# LEDDimmerDuoMiniSwitchReg.net
KiCad netlist of a schematic drawn in EAGLE
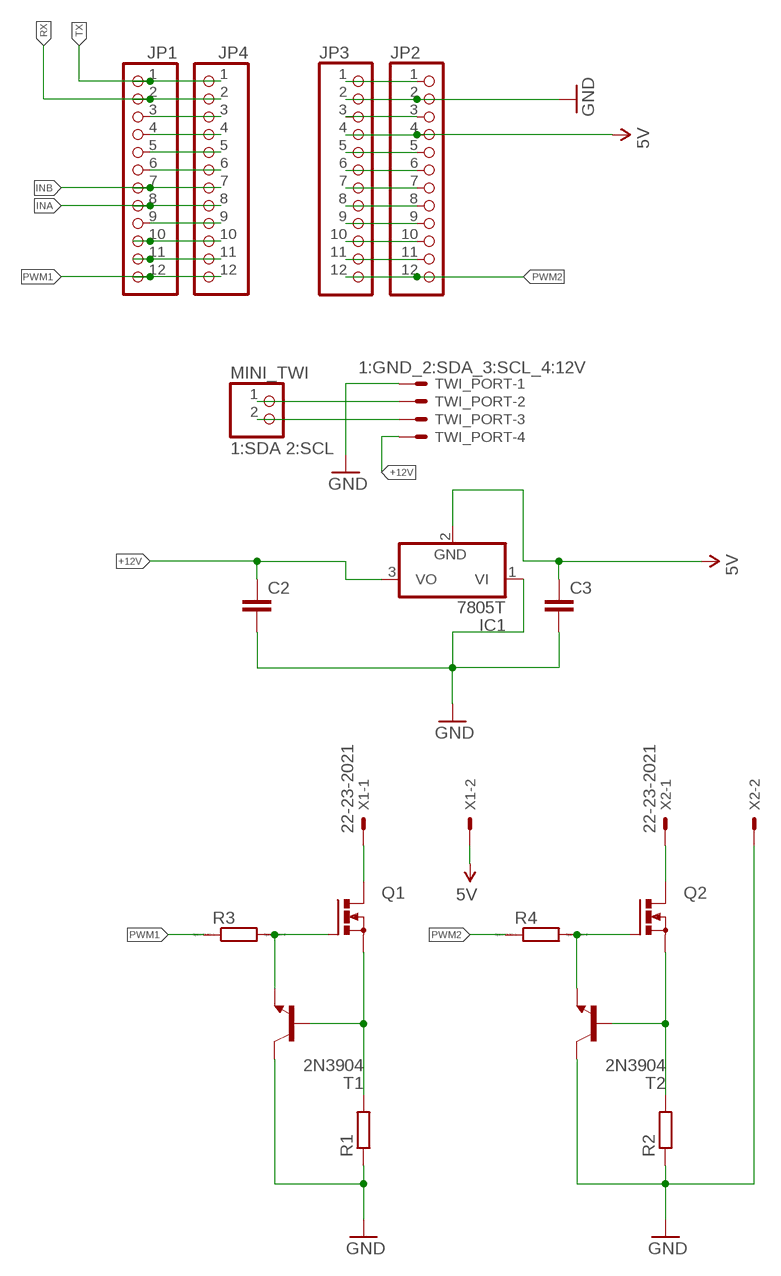
[diagram p0: schematic, sheet 1]

(export (version "E")
  (design (tool "Eeschema 10.0.6"))
  (components
    (comp (ref "C2")
      (value "CAP0603-CAP")
      (footprint "eagle-import:0603-CAP")
      (libsource (lib "eagle-import") (part "CAP0603-CAP"))
    )
    (comp (ref "C3")
      (value "CAP0603-CAP")
      (footprint "eagle-import:0603-CAP")
      (libsource (lib "eagle-import") (part "CAP0603-CAP"))
    )
    (comp (ref "IC1")
      (value "7805T")
      (footprint "eagle-import:TO220H")
      (libsource (lib "eagle-import") (part "78T05"))
    )
    (comp (ref "JP1")
      (value "PINHD-1X12")
      (footprint "eagle-import:1X12")
      (libsource (lib "eagle-import") (part "PINHD-1X12"))
    )
    (comp (ref "JP2")
      (value "PINHD-1X12")
      (footprint "eagle-import:1X12")
      (libsource (lib "eagle-import") (part "PINHD-1X12"))
    )
    (comp (ref "JP3")
      (value "PINHD-1X12")
      (footprint "eagle-import:1X12")
      (libsource (lib "eagle-import") (part "PINHD-1X12"))
    )
    (comp (ref "JP4")
      (value "PINHD-1X12")
      (footprint "eagle-import:1X12")
      (libsource (lib "eagle-import") (part "PINHD-1X12"))
    )
    (comp (ref "MINI_TWI")
      (value "1:SDA 2:SCL")
      (footprint "eagle-import:1X02")
      (libsource (lib "eagle-import") (part "PINHD-1X2"))
    )
    (comp (ref "Q1")
      (value "PMOSFET_NTO220BV")
      (footprint "eagle-import:TO220BV")
      (libsource (lib "eagle-import") (part "PMOSFET_NTO220BV"))
    )
    (comp (ref "Q2")
      (value "PMOSFET_NTO220BV")
      (footprint "eagle-import:TO220BV")
      (libsource (lib "eagle-import") (part "PMOSFET_NTO220BV"))
    )
    (comp (ref "R1")
      (value "R-EU_VTA52")
      (footprint "eagle-import:VTA52")
      (libsource (lib "eagle-import") (part "R-EU_VTA52"))
    )
    (comp (ref "R2")
      (value "R-EU_VTA52")
      (footprint "eagle-import:VTA52")
      (libsource (lib "eagle-import") (part "R-EU_VTA52"))
    )
    (comp (ref "R3") (value "R") (footprint "eagle-import:R0805") (libsource (lib "eagle-import") (part "R")))
    (comp (ref "R4") (value "R") (footprint "eagle-import:R0805") (libsource (lib "eagle-import") (part "R")))
    (comp (ref "T1")
      (value "2N3904")
      (footprint "eagle-import:TO92")
      (libsource (lib "eagle-import") (part "2N3904"))
    )
    (comp (ref "T2")
      (value "2N3904")
      (footprint "eagle-import:TO92")
      (libsource (lib "eagle-import") (part "2N3904"))
    )
    (comp (ref "TWI_PORT")
      (value "1:GND_2:SDA_3:SCL_4:12V")
      (footprint "eagle-import:22-23-2041")
      (fields (field (name "MF") "MOLEX") (field (name "MPN") "22-23-2041"))
      (libsource (lib "eagle-import") (part "22-23-2041"))
    )
    (comp (ref "X1")
      (value "22-23-2021")
      (footprint "eagle-import:22-23-2021")
      (fields (field (name "MF") "MOLEX"))
      (libsource (lib "eagle-import") (part "22-23-2021"))
    )
    (comp (ref "X2")
      (value "22-23-2021")
      (footprint "eagle-import:22-23-2021")
      (fields (field (name "MF") "MOLEX"))
      (libsource (lib "eagle-import") (part "22-23-2021"))
    )
  )
  (nets
    (net (code "1") (name "+12V") (class "Default")
      (node (ref "C2") (pin "1") (pinfunction "1_1") (pintype "passive"))
      (node (ref "IC1") (pin "3") (pinfunction "VO_3") (pintype "passive"))
      (node (ref "TWI_PORT") (pin "4") (pinfunction "S_4") (pintype "passive"))
    )
    (net (code "2") (name "5V") (class "Default")
      (node (ref "C3") (pin "1") (pinfunction "1_1") (pintype "passive"))
      (node (ref "IC1") (pin "2") (pinfunction "GND_2") (pintype "passive"))
      (node (ref "JP2") (pin "4") (pinfunction "4_4") (pintype "passive"))
      (node (ref "JP3") (pin "4") (pinfunction "4_4") (pintype "passive"))
      (node (ref "X1") (pin "2") (pinfunction "S_2") (pintype "passive"))
    )
    (net (code "3") (name "GND") (class "Default")
      (node (ref "C2") (pin "2") (pinfunction "2_2") (pintype "passive"))
      (node (ref "C3") (pin "2") (pinfunction "2_2") (pintype "passive"))
      (node (ref "IC1") (pin "1") (pinfunction "VI_1") (pintype "input"))
      (node (ref "JP2") (pin "2") (pinfunction "2_2") (pintype "passive"))
      (node (ref "JP3") (pin "2") (pinfunction "2_2") (pintype "passive"))
      (node (ref "R1") (pin "1") (pinfunction "1_1") (pintype "passive"))
      (node (ref "R2") (pin "1") (pinfunction "1_1") (pintype "passive"))
      (node (ref "T1") (pin "1") (pinfunction "C_1") (pintype "passive"))
      (node (ref "T2") (pin "1") (pinfunction "C_1") (pintype "passive"))
      (node (ref "TWI_PORT") (pin "1") (pinfunction "S_1") (pintype "passive"))
      (node (ref "X2") (pin "2") (pinfunction "S_2") (pintype "passive"))
    )
    (net (code "4") (name "INA") (class "Default")
      (node (ref "JP1") (pin "8") (pinfunction "8_8") (pintype "passive"))
      (node (ref "JP4") (pin "8") (pinfunction "8_8") (pintype "passive"))
    )
    (net (code "5") (name "INB") (class "Default")
      (node (ref "JP1") (pin "7") (pinfunction "7_7") (pintype "passive"))
      (node (ref "JP4") (pin "7") (pinfunction "7_7") (pintype "passive"))
    )
    (net (code "6") (name "Net-(JP1-Pad3)") (class "Default")
      (node (ref "JP1") (pin "3") (pinfunction "3_3") (pintype "passive"))
      (node (ref "JP4") (pin "3") (pinfunction "3_3") (pintype "passive"))
    )
    (net (code "7") (name "Net-(JP1-Pad4)") (class "Default")
      (node (ref "JP1") (pin "4") (pinfunction "4_4") (pintype "passive"))
      (node (ref "JP4") (pin "4") (pinfunction "4_4") (pintype "passive"))
    )
    (net (code "8") (name "Net-(JP1-Pad5)") (class "Default")
      (node (ref "JP1") (pin "5") (pinfunction "5_5") (pintype "passive"))
      (node (ref "JP4") (pin "5") (pinfunction "5_5") (pintype "passive"))
    )
    (net (code "9") (name "Net-(JP1-Pad6)") (class "Default")
      (node (ref "JP1") (pin "6") (pinfunction "6_6") (pintype "passive"))
      (node (ref "JP4") (pin "6") (pinfunction "6_6") (pintype "passive"))
    )
    (net (code "10") (name "Net-(JP1-Pad9)") (class "Default")
      (node (ref "JP1") (pin "9") (pinfunction "9_9") (pintype "passive"))
      (node (ref "JP4") (pin "9") (pinfunction "9_9") (pintype "passive"))
    )
    (net (code "11") (name "Net-(JP1-Pad10)") (class "Default")
      (node (ref "JP1") (pin "10") (pinfunction "10_10") (pintype "passive"))
      (node (ref "JP4") (pin "10") (pinfunction "10_10") (pintype "passive"))
    )
    (net (code "12") (name "Net-(JP1-Pad11)") (class "Default")
      (node (ref "JP1") (pin "11") (pinfunction "11_11") (pintype "passive"))
      (node (ref "JP4") (pin "11") (pinfunction "11_11") (pintype "passive"))
    )
    (net (code "13") (name "Net-(JP2-Pad1)") (class "Default")
      (node (ref "JP2") (pin "1") (pinfunction "1_1") (pintype "passive"))
      (node (ref "JP3") (pin "1") (pinfunction "1_1") (pintype "passive"))
    )
    (net (code "14") (name "Net-(JP2-Pad3)") (class "Default")
      (node (ref "JP2") (pin "3") (pinfunction "3_3") (pintype "passive"))
      (node (ref "JP3") (pin "3") (pinfunction "3_3") (pintype "passive"))
    )
    (net (code "15") (name "Net-(JP2-Pad5)") (class "Default")
      (node (ref "JP2") (pin "5") (pinfunction "5_5") (pintype "passive"))
      (node (ref "JP3") (pin "5") (pinfunction "5_5") (pintype "passive"))
    )
    (net (code "16") (name "Net-(JP2-Pad6)") (class "Default")
      (node (ref "JP2") (pin "6") (pinfunction "6_6") (pintype "passive"))
      (node (ref "JP3") (pin "6") (pinfunction "6_6") (pintype "passive"))
    )
    (net (code "17") (name "Net-(JP2-Pad7)") (class "Default")
      (node (ref "JP2") (pin "7") (pinfunction "7_7") (pintype "passive"))
      (node (ref "JP3") (pin "7") (pinfunction "7_7") (pintype "passive"))
    )
    (net (code "18") (name "Net-(JP2-Pad8)") (class "Default")
      (node (ref "JP2") (pin "8") (pinfunction "8_8") (pintype "passive"))
      (node (ref "JP3") (pin "8") (pinfunction "8_8") (pintype "passive"))
    )
    (net (code "19") (name "Net-(JP2-Pad9)") (class "Default")
      (node (ref "JP2") (pin "9") (pinfunction "9_9") (pintype "passive"))
      (node (ref "JP3") (pin "9") (pinfunction "9_9") (pintype "passive"))
    )
    (net (code "20") (name "Net-(JP2-Pad10)") (class "Default")
      (node (ref "JP2") (pin "10") (pinfunction "10_10") (pintype "passive"))
      (node (ref "JP3") (pin "10") (pinfunction "10_10") (pintype "passive"))
    )
    (net (code "21") (name "Net-(JP2-Pad11)") (class "Default")
      (node (ref "JP2") (pin "11") (pinfunction "11_11") (pintype "passive"))
      (node (ref "JP3") (pin "11") (pinfunction "11_11") (pintype "passive"))
    )
    (net (code "22") (name "Net-(T1-B)") (class "Default")
      (node (ref "Q1") (pin "S") (pinfunction "S_S") (pintype "passive"))
      (node (ref "R1") (pin "2") (pinfunction "2_2") (pintype "passive"))
      (node (ref "T1") (pin "2") (pinfunction "B_2") (pintype "passive"))
    )
    (net (code "23") (name "Net-(T2-B)") (class "Default")
      (node (ref "Q2") (pin "S") (pinfunction "S_S") (pintype "passive"))
      (node (ref "R2") (pin "2") (pinfunction "2_2") (pintype "passive"))
      (node (ref "T2") (pin "2") (pinfunction "B_2") (pintype "passive"))
    )
    (net (code "24") (name "Net-(T2-E)") (class "Default")
      (node (ref "Q2") (pin "G") (pinfunction "G_G") (pintype "passive"))
      (node (ref "R4") (pin "2") (pinfunction "2_2") (pintype "passive"))
      (node (ref "T2") (pin "3") (pinfunction "E_3") (pintype "passive"))
    )
    (net (code "25") (name "Net-(TWI_PORTB-S)") (class "Default")
      (node (ref "MINI_TWI") (pin "1") (pinfunction "1_1") (pintype "passive"))
      (node (ref "TWI_PORT") (pin "2") (pinfunction "S_2") (pintype "passive"))
    )
    (net (code "26") (name "Net-(TWI_PORTC-S)") (class "Default")
      (node (ref "MINI_TWI") (pin "2") (pinfunction "2_2") (pintype "passive"))
      (node (ref "TWI_PORT") (pin "3") (pinfunction "S_3") (pintype "passive"))
    )
    (net (code "27") (name "Net-(X1A-S)") (class "Default")
      (node (ref "Q1") (pin "D") (pinfunction "D_D") (pintype "passive"))
      (node (ref "X1") (pin "1") (pinfunction "S_1") (pintype "passive"))
    )
    (net (code "28") (name "Net-(X2A-S)") (class "Default")
      (node (ref "Q2") (pin "D") (pinfunction "D_D") (pintype "passive"))
      (node (ref "X2") (pin "1") (pinfunction "S_1") (pintype "passive"))
    )
    (net (code "29") (name "PWM1") (class "Default")
      (node (ref "JP1") (pin "12") (pinfunction "12_12") (pintype "passive"))
      (node (ref "JP4") (pin "12") (pinfunction "12_12") (pintype "passive"))
      (node (ref "Q1") (pin "G") (pinfunction "G_G") (pintype "passive"))
      (node (ref "R3") (pin "1") (pinfunction "1_1") (pintype "passive"))
      (node (ref "R3") (pin "2") (pinfunction "2_2") (pintype "passive"))
      (node (ref "T1") (pin "3") (pinfunction "E_3") (pintype "passive"))
    )
    (net (code "30") (name "PWM2") (class "Default")
      (node (ref "JP2") (pin "12") (pinfunction "12_12") (pintype "passive"))
      (node (ref "JP3") (pin "12") (pinfunction "12_12") (pintype "passive"))
      (node (ref "R4") (pin "1") (pinfunction "1_1") (pintype "passive"))
    )
    (net (code "31") (name "RX") (class "Default")
      (node (ref "JP1") (pin "2") (pinfunction "2_2") (pintype "passive"))
      (node (ref "JP4") (pin "2") (pinfunction "2_2") (pintype "passive"))
    )
    (net (code "32") (name "TX") (class "Default")
      (node (ref "JP1") (pin "1") (pinfunction "1_1") (pintype "passive"))
      (node (ref "JP4") (pin "1") (pinfunction "1_1") (pintype "passive"))
    )
  )
)
